# W5500-ESP32c3-supermini.net
KiCad netlist of a schematic drawn in EasyEDA Pro
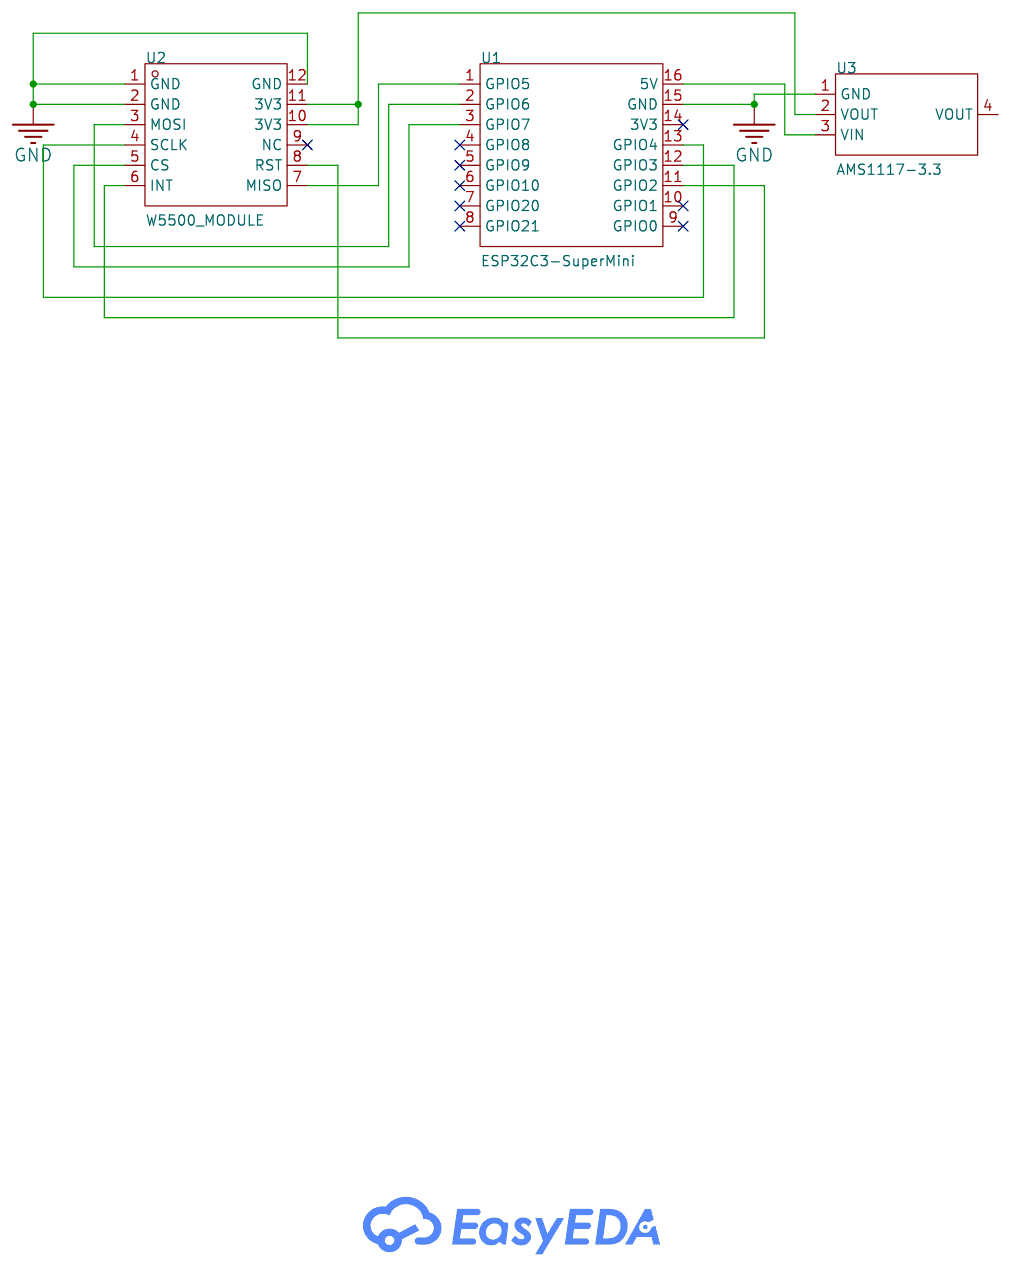
[diagram p0: schematic sheet]

(export (version "E")
  (design (tool "Eeschema 10.0.6"))
  (components
    (comp (ref "U1")
      (value "ESP32C3-SuperMini")
      (footprint "easyedapro:COMM-SMD_16P-L22.5-W18.0-P2.54-TL")
      (libsource (lib "easyedapro") (part "ESP32C3-SUPERMINI"))
    )
    (comp (ref "U2")
      (value "W5500_MODULE")
      (footprint "easyedapro:COMM-TH_L25.0-W23.0_W5500_MODULE")
      (libsource (lib "easyedapro") (part "W5500_MODULE"))
    )
    (comp (ref "U3")
      (value "AMS1117-3.3")
      (footprint "easyedapro:SOT-223-3_L6.5-W3.4-P2.30-LS7.0-BR")
      (fields (field (name "Manufacturer") "AMS"))
      (libsource (lib "easyedapro") (part "AMS1117-3.3"))
    )
  )
  (nets
    (net (code "1") (name "GND") (class "Default")
      (node (ref "U1") (pin "15") (pinfunction "GND_15") (pintype "unspecified"))
      (node (ref "U2") (pin "1") (pinfunction "GND_1") (pintype "unspecified"))
      (node (ref "U2") (pin "12") (pinfunction "GND_12") (pintype "unspecified"))
      (node (ref "U2") (pin "2") (pinfunction "GND_2") (pintype "unspecified"))
      (node (ref "U3") (pin "1") (pinfunction "GND_1") (pintype "unspecified"))
    )
    (net (code "2") (name "Net-(U1-5V)") (class "Default")
      (node (ref "U1") (pin "16") (pinfunction "5V_16") (pintype "unspecified"))
      (node (ref "U3") (pin "3") (pinfunction "VIN_3") (pintype "unspecified"))
    )
    (net (code "3") (name "Net-(U1-GPIO2)") (class "Default")
      (node (ref "U1") (pin "11") (pinfunction "GPIO2_11") (pintype "unspecified"))
      (node (ref "U2") (pin "8") (pinfunction "RST_8") (pintype "unspecified"))
    )
    (net (code "4") (name "Net-(U1-GPIO3)") (class "Default")
      (node (ref "U1") (pin "12") (pinfunction "GPIO3_12") (pintype "unspecified"))
      (node (ref "U2") (pin "6") (pinfunction "INT_6") (pintype "unspecified"))
    )
    (net (code "5") (name "Net-(U1-GPIO4)") (class "Default")
      (node (ref "U1") (pin "13") (pinfunction "GPIO4_13") (pintype "unspecified"))
      (node (ref "U2") (pin "4") (pinfunction "SCLK_4") (pintype "unspecified"))
    )
    (net (code "6") (name "Net-(U1-GPIO5)") (class "Default")
      (node (ref "U1") (pin "1") (pinfunction "GPIO5_1") (pintype "unspecified"))
      (node (ref "U2") (pin "7") (pinfunction "MISO_7") (pintype "unspecified"))
    )
    (net (code "7") (name "Net-(U1-GPIO6)") (class "Default")
      (node (ref "U1") (pin "2") (pinfunction "GPIO6_2") (pintype "unspecified"))
      (node (ref "U2") (pin "3") (pinfunction "MOSI_3") (pintype "unspecified"))
    )
    (net (code "8") (name "Net-(U1-GPIO7)") (class "Default")
      (node (ref "U1") (pin "3") (pinfunction "GPIO7_3") (pintype "unspecified"))
      (node (ref "U2") (pin "5") (pinfunction "CS_5") (pintype "unspecified"))
    )
    (net (code "9") (name "Net-(U2-3V3-Pad10)") (class "Default")
      (node (ref "U2") (pin "10") (pinfunction "3V3_10") (pintype "unspecified"))
      (node (ref "U2") (pin "11") (pinfunction "3V3_11") (pintype "unspecified"))
      (node (ref "U3") (pin "2") (pinfunction "VOUT_2") (pintype "unspecified"))
    )
    (net (code "10") (name "unconnected-(U1-3V3-Pad14)") (class "Default")
      (node (ref "U1") (pin "14") (pinfunction "3V3_14") (pintype "unspecified+no_connect"))
    )
    (net (code "11") (name "unconnected-(U1-GPIO0-Pad9)") (class "Default")
      (node (ref "U1") (pin "9") (pinfunction "GPIO0_9") (pintype "unspecified+no_connect"))
    )
    (net (code "12") (name "unconnected-(U1-GPIO1-Pad10)") (class "Default")
      (node (ref "U1") (pin "10") (pinfunction "GPIO1_10") (pintype "unspecified+no_connect"))
    )
    (net (code "13") (name "unconnected-(U1-GPIO8-Pad4)") (class "Default")
      (node (ref "U1") (pin "4") (pinfunction "GPIO8_4") (pintype "unspecified+no_connect"))
    )
    (net (code "14") (name "unconnected-(U1-GPIO9-Pad5)") (class "Default")
      (node (ref "U1") (pin "5") (pinfunction "GPIO9_5") (pintype "unspecified+no_connect"))
    )
    (net (code "15") (name "unconnected-(U1-GPIO10-Pad6)") (class "Default")
      (node (ref "U1") (pin "6") (pinfunction "GPIO10_6") (pintype "unspecified+no_connect"))
    )
    (net (code "16") (name "unconnected-(U1-GPIO20-Pad7)") (class "Default")
      (node (ref "U1") (pin "7") (pinfunction "GPIO20_7") (pintype "unspecified+no_connect"))
    )
    (net (code "17") (name "unconnected-(U1-GPIO21-Pad8)") (class "Default")
      (node (ref "U1") (pin "8") (pinfunction "GPIO21_8") (pintype "unspecified+no_connect"))
    )
    (net (code "18") (name "unconnected-(U2-NC-Pad9)") (class "Default")
      (node (ref "U2") (pin "9") (pinfunction "NC_9") (pintype "unspecified+no_connect"))
    )
    (net (code "19") (name "unconnected-(U3-VOUT-Pad4)") (class "Default")
      (node (ref "U3") (pin "4") (pinfunction "VOUT_4") (pintype "unspecified"))
    )
  )
)
